# ETH_1G_MAGNET_RJ45MIDMNT.net
KiCad netlist of a schematic drawn in Altium Designer
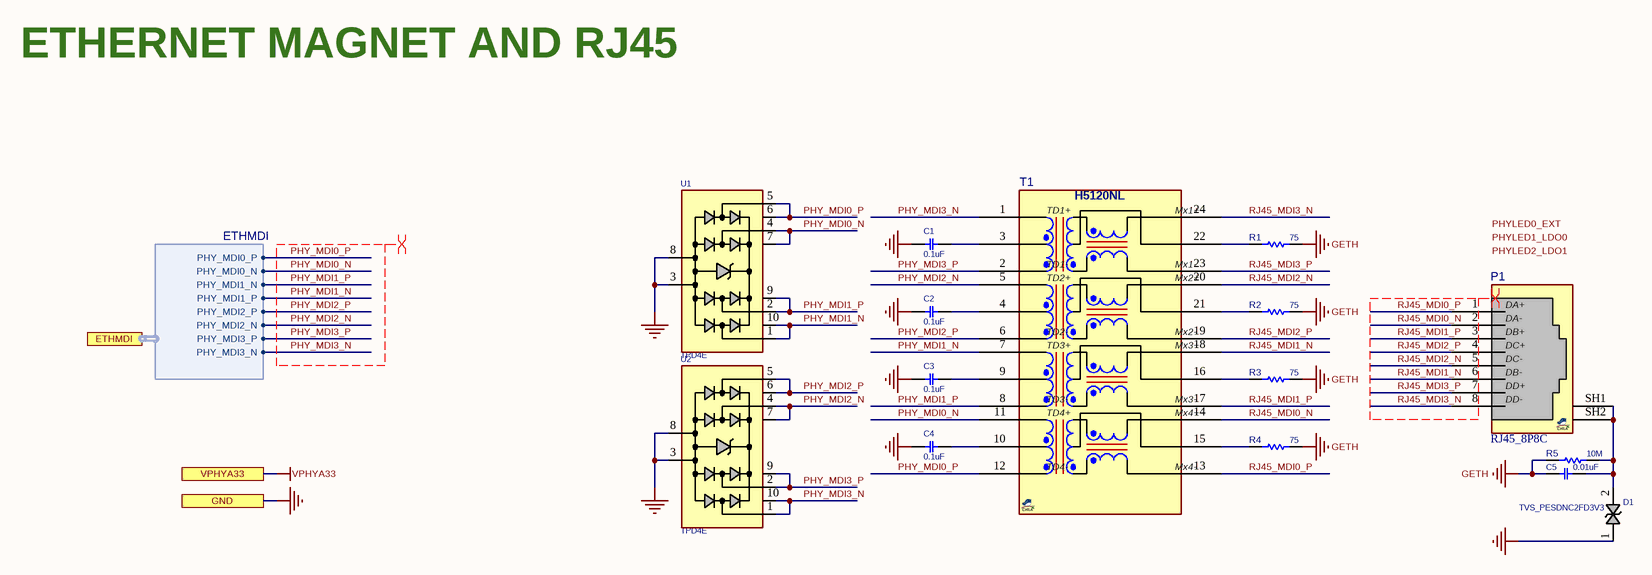
[diagram p0: ETH_1G_MAGNET_RJ45MIDMNT.SchDoc]

(export (version "E")
  (design (tool "Eeschema 10.0.6"))
  (components
    (comp (ref "C1")
      (value "0.1uF")
      (footprint "C0402")
      (description "CAP, MLCC")
      (fields (field (name "MANF_P#") "GRM155R61E104") (field (name "MANF") "Murata"))
      (libsource (lib "mlcc_smd_passive") (part "CAP_SMD_MLCC_100n50T"))
    )
    (comp (ref "C2")
      (value "0.1uF")
      (footprint "C0402")
      (description "CAP, MLCC")
      (fields (field (name "MANF_P#") "GRM155R61E104") (field (name "MANF") "Murata"))
      (libsource (lib "mlcc_smd_passive") (part "CAP_SMD_MLCC_100n50T"))
    )
    (comp (ref "C3")
      (value "0.1uF")
      (footprint "C0402")
      (description "CAP, MLCC")
      (fields (field (name "MANF_P#") "GRM155R61E104") (field (name "MANF") "Murata"))
      (libsource (lib "mlcc_smd_passive") (part "CAP_SMD_MLCC_100n50T"))
    )
    (comp (ref "C4")
      (value "0.1uF")
      (footprint "C0402")
      (description "CAP, MLCC")
      (fields (field (name "MANF_P#") "GRM155R61E104") (field (name "MANF") "Murata"))
      (libsource (lib "mlcc_smd_passive") (part "CAP_SMD_MLCC_100n50T"))
    )
    (comp (ref "C5")
      (value "0.01uF")
      (footprint "C1210")
      (description "CAP, MLCC")
      (libsource (lib "mlcc_smd_passive") (part "CAP_SMD_MLCC_100n50T"))
    )
    (comp (ref "D1")
      (value "TVS_PESDNC2FD3V3")
      (footprint "ESD0402")
      (description "TVS, ESD PROTECT, Bidirectional")
      (fields (field (name "MANF_P#") "PESDNC2FD3V3BS"))
      (libsource (lib "protect_tvs_esd_fuse") (part "TVS_PESDNC2FD3V3"))
    )
    (comp (ref "P1")
      (value "RJ45_8P8C")
      (footprint "RJ45_8S_RA_TD_SMD")
      (description "RJ45, 8P, SHIELDED, RightAngle, TabDown, SMDEMI panel ground")
      (fields (field (name "MANF") "Heling") (field (name "MANF_P#") "MJ88-B011-JRVS1-P"))
      (libsource (lib "conn_rj_ModularJack") (part "RJ45_8S_RA_TD_SMD"))
    )
    (comp (ref "R1")
      (value "75")
      (footprint "R0402")
      (description "RESISTOR, SMD")
      (libsource (lib "passive_res_smd") (part "RES_SMD"))
    )
    (comp (ref "R2")
      (value "75")
      (footprint "R0402")
      (description "RESISTOR, SMD")
      (libsource (lib "passive_res_smd") (part "RES_SMD"))
    )
    (comp (ref "R3")
      (value "75")
      (footprint "R0402")
      (description "RESISTOR, SMD")
      (libsource (lib "passive_res_smd") (part "RES_SMD"))
    )
    (comp (ref "R4")
      (value "75")
      (footprint "R0402")
      (description "RESISTOR, SMD")
      (libsource (lib "passive_res_smd") (part "RES_SMD"))
    )
    (comp (ref "R5")
      (value "10M")
      (footprint "R1206")
      (description "RESISTOR, SMD")
      (libsource (lib "passive_res_smd") (part "RES_SMD"))
    )
    (comp (ref "T1")
      (value "H5120NL")
      (footprint "SO_24_9W2H")
      (description "Transformer, LAN, 1000 Base-T, 1CT:1CT, 350uH")
      (fields (field (name "MANF") "Pulse, link-pp") (field (name "MANF_P#") "H5120NL, LP82453NL"))
      (libsource (lib "transformer_ethernet") (part "H5120NL_SO24"))
    )
    (comp (ref "U1")
      (value "TPD4E")
      (footprint "SON50_10_2510")
      (description "TVS, ESD PROTECT, 4CH,")
      (fields (field (name "MANF_P#") "TPD4E05U06DQA") (field (name "MANF") "Texas Instruments"))
      (libsource (lib "protect_tvs_esd_fuse") (part "TVS_X4_TPD4E05U06"))
    )
    (comp (ref "U2")
      (value "TPD4E")
      (footprint "SON50_10_2510")
      (description "TVS, ESD PROTECT, 4CH,")
      (fields (field (name "MANF_P#") "TPD4E05U06DQA") (field (name "MANF") "Texas Instruments"))
      (libsource (lib "protect_tvs_esd_fuse") (part "TVS_X4_TPD4E05U06"))
    )
  )
  (nets
    (net (code "5") (name "/PHY_MDI0_N") (class "Default")
      (node (ref "T1") (pin "11") (pinfunction "TD4+_11") (pintype "passive"))
      (node (ref "U1") (pin "4") (pinfunction "4_4") (pintype "passive"))
      (node (ref "U1") (pin "7") (pinfunction "7_7") (pintype "passive"))
    )
    (net (code "6") (name "/PHY_MDI0_P") (class "Default")
      (node (ref "T1") (pin "12") (pinfunction "TD4-_12") (pintype "passive"))
      (node (ref "U1") (pin "5") (pinfunction "5_5") (pintype "passive"))
      (node (ref "U1") (pin "6") (pinfunction "6_6") (pintype "passive"))
    )
    (net (code "7") (name "/PHY_MDI1_N") (class "Default")
      (node (ref "T1") (pin "7") (pinfunction "TD3+_7") (pintype "passive"))
      (node (ref "U1") (pin "1") (pinfunction "1_1") (pintype "passive"))
      (node (ref "U1") (pin "10") (pinfunction "10_10") (pintype "passive"))
    )
    (net (code "8") (name "/PHY_MDI1_P") (class "Default")
      (node (ref "T1") (pin "8") (pinfunction "TD3-_8") (pintype "passive"))
      (node (ref "U1") (pin "2") (pinfunction "2_2") (pintype "passive"))
      (node (ref "U1") (pin "9") (pinfunction "9_9") (pintype "passive"))
    )
    (net (code "9") (name "/PHY_MDI2_N") (class "Default")
      (node (ref "T1") (pin "5") (pinfunction "TD2+_5") (pintype "passive"))
      (node (ref "U2") (pin "4") (pinfunction "4_4") (pintype "passive"))
      (node (ref "U2") (pin "7") (pinfunction "7_7") (pintype "passive"))
    )
    (net (code "10") (name "/PHY_MDI2_P") (class "Default")
      (node (ref "T1") (pin "6") (pinfunction "TD2-_6") (pintype "passive"))
      (node (ref "U2") (pin "5") (pinfunction "5_5") (pintype "passive"))
      (node (ref "U2") (pin "6") (pinfunction "6_6") (pintype "passive"))
    )
    (net (code "11") (name "/PHY_MDI3_N") (class "Default")
      (node (ref "T1") (pin "1") (pinfunction "TD1+_1") (pintype "passive"))
      (node (ref "U2") (pin "1") (pinfunction "1_1") (pintype "passive"))
      (node (ref "U2") (pin "10") (pinfunction "10_10") (pintype "passive"))
    )
    (net (code "12") (name "/PHY_MDI3_P") (class "Default")
      (node (ref "T1") (pin "2") (pinfunction "TD1-_2") (pintype "passive"))
      (node (ref "U2") (pin "2") (pinfunction "2_2") (pintype "passive"))
      (node (ref "U2") (pin "9") (pinfunction "9_9") (pintype "passive"))
    )
    (net (code "13") (name "/RJ45_MDI0_N") (class "Default")
      (node (ref "P1") (pin "2") (pinfunction "DA-_2") (pintype "passive"))
      (node (ref "T1") (pin "14") (pinfunction "MX4+_14") (pintype "passive"))
    )
    (net (code "14") (name "/RJ45_MDI0_P") (class "Default")
      (node (ref "P1") (pin "1") (pinfunction "DA+_1") (pintype "passive"))
      (node (ref "T1") (pin "13") (pinfunction "MX4-_13") (pintype "passive"))
    )
    (net (code "15") (name "/RJ45_MDI1_N") (class "Default")
      (node (ref "P1") (pin "6") (pinfunction "DB-_6") (pintype "passive"))
      (node (ref "T1") (pin "18") (pinfunction "MX3+_18") (pintype "passive"))
    )
    (net (code "16") (name "/RJ45_MDI1_P") (class "Default")
      (node (ref "P1") (pin "3") (pinfunction "DB+_3") (pintype "passive"))
      (node (ref "T1") (pin "17") (pinfunction "MX3-_17") (pintype "passive"))
    )
    (net (code "17") (name "/RJ45_MDI2_N") (class "Default")
      (node (ref "P1") (pin "5") (pinfunction "DC-_5") (pintype "passive"))
      (node (ref "T1") (pin "20") (pinfunction "MX2+_20") (pintype "passive"))
    )
    (net (code "18") (name "/RJ45_MDI2_P") (class "Default")
      (node (ref "P1") (pin "4") (pinfunction "DC+_4") (pintype "passive"))
      (node (ref "T1") (pin "19") (pinfunction "MX2-_19") (pintype "passive"))
    )
    (net (code "19") (name "/RJ45_MDI3_N") (class "Default")
      (node (ref "P1") (pin "8") (pinfunction "DD-_8") (pintype "passive"))
      (node (ref "T1") (pin "24") (pinfunction "MX1+_24") (pintype "passive"))
    )
    (net (code "20") (name "/RJ45_MDI3_P") (class "Default")
      (node (ref "P1") (pin "7") (pinfunction "DD+_7") (pintype "passive"))
      (node (ref "T1") (pin "23") (pinfunction "MX1-_23") (pintype "passive"))
    )
    (net (code "22") (name "GETH") (class "Default")
      (node (ref "C5") (pin "1") (pinfunction "1_1") (pintype "passive"))
      (node (ref "R1") (pin "1") (pinfunction "1_1") (pintype "passive"))
      (node (ref "R2") (pin "1") (pinfunction "1_1") (pintype "passive"))
      (node (ref "R3") (pin "1") (pinfunction "1_1") (pintype "passive"))
      (node (ref "R4") (pin "1") (pinfunction "1_1") (pintype "passive"))
      (node (ref "R5") (pin "2") (pinfunction "2_2") (pintype "passive"))
    )
    (net (code "23") (name "GND") (class "Default")
      (node (ref "C1") (pin "1") (pinfunction "1_1") (pintype "passive"))
      (node (ref "C2") (pin "1") (pinfunction "1_1") (pintype "passive"))
      (node (ref "C3") (pin "1") (pinfunction "1_1") (pintype "passive"))
      (node (ref "C4") (pin "1") (pinfunction "1_1") (pintype "passive"))
      (node (ref "D1") (pin "1") (pinfunction "1_1") (pintype "passive"))
      (node (ref "U1") (pin "3") (pinfunction "3_3") (pintype "passive"))
      (node (ref "U1") (pin "8") (pinfunction "8_8") (pintype "passive"))
      (node (ref "U2") (pin "3") (pinfunction "3_3") (pintype "passive"))
      (node (ref "U2") (pin "8") (pinfunction "8_8") (pintype "passive"))
    )
    (net (code "24") (name "Net-(C5-Pad2)") (class "Default")
      (node (ref "C5") (pin "2") (pinfunction "2_2") (pintype "passive"))
      (node (ref "D1") (pin "2") (pinfunction "2_2") (pintype "passive"))
      (node (ref "P1") (pin "SH1") (pinfunction "SH1_SH1") (pintype "passive"))
      (node (ref "P1") (pin "SH2") (pinfunction "SH2_SH2") (pintype "passive"))
      (node (ref "R5") (pin "1") (pinfunction "1_1") (pintype "passive"))
    )
    (net (code "25") (name "Net-(T1-MCT1)") (class "Default")
      (node (ref "R1") (pin "2") (pinfunction "2_2") (pintype "passive"))
      (node (ref "T1") (pin "22") (pinfunction "MCT1_22") (pintype "passive"))
    )
    (net (code "26") (name "Net-(T1-MCT2)") (class "Default")
      (node (ref "R2") (pin "2") (pinfunction "2_2") (pintype "passive"))
      (node (ref "T1") (pin "21") (pinfunction "MCT2_21") (pintype "passive"))
    )
    (net (code "27") (name "Net-(T1-MCT3)") (class "Default")
      (node (ref "R3") (pin "2") (pinfunction "2_2") (pintype "passive"))
      (node (ref "T1") (pin "16") (pinfunction "MCT3_16") (pintype "passive"))
    )
    (net (code "28") (name "Net-(T1-MCT4)") (class "Default")
      (node (ref "R4") (pin "2") (pinfunction "2_2") (pintype "passive"))
      (node (ref "T1") (pin "15") (pinfunction "MCT4_15") (pintype "passive"))
    )
    (net (code "29") (name "Net-(T1-TCT1)") (class "Default")
      (node (ref "C1") (pin "2") (pinfunction "2_2") (pintype "passive"))
      (node (ref "T1") (pin "3") (pinfunction "TCT1_3") (pintype "passive"))
    )
    (net (code "30") (name "Net-(T1-TCT2)") (class "Default")
      (node (ref "C2") (pin "2") (pinfunction "2_2") (pintype "passive"))
      (node (ref "T1") (pin "4") (pinfunction "TCT2_4") (pintype "passive"))
    )
    (net (code "31") (name "Net-(T1-TCT3)") (class "Default")
      (node (ref "C3") (pin "2") (pinfunction "2_2") (pintype "passive"))
      (node (ref "T1") (pin "9") (pinfunction "TCT3_9") (pintype "passive"))
    )
    (net (code "32") (name "Net-(T1-TCT4)") (class "Default")
      (node (ref "C4") (pin "2") (pinfunction "2_2") (pintype "passive"))
      (node (ref "T1") (pin "10") (pinfunction "TCT4_10") (pintype "passive"))
    )
  )
)
